# basic_schematic.net
KiCad netlist of a schematic drawn in EAGLE
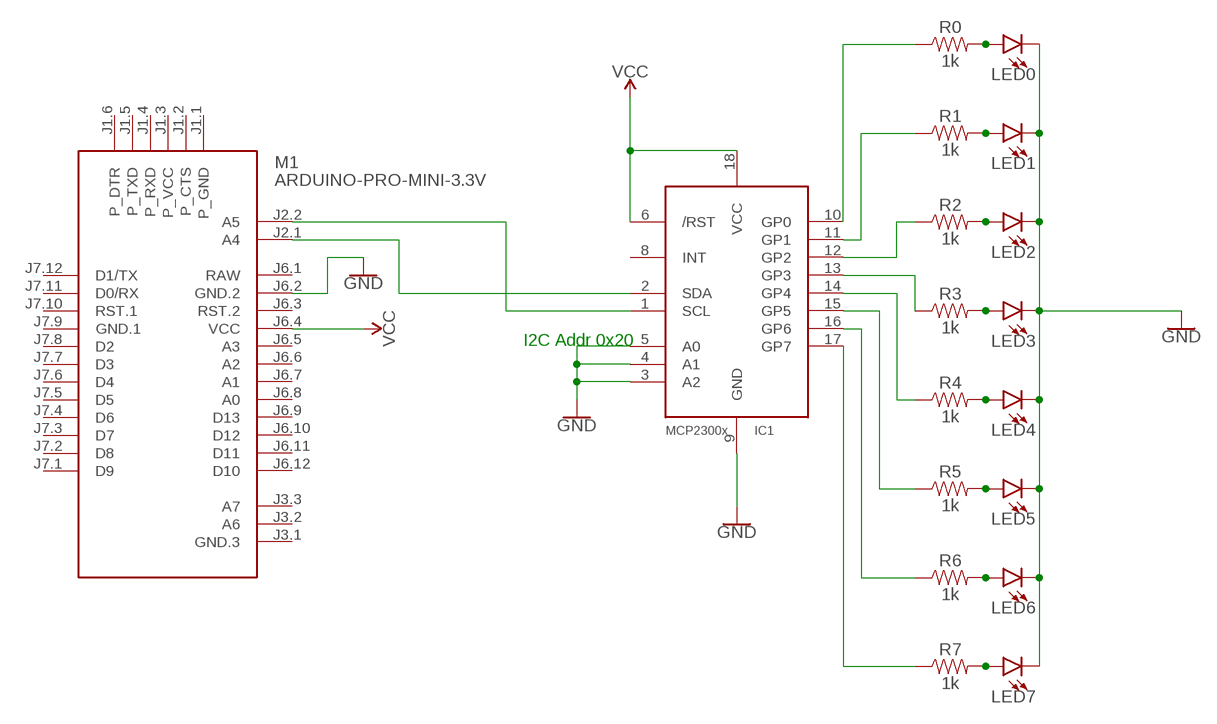
[diagram p0: schematic, sheet 1]

(export (version "E")
  (design (tool "Eeschema 10.0.6"))
  (components
    (comp (ref "IC1")
      (value "MCP23008/SO")
      (footprint "eagle-import:SO18W")
      (libsource (lib "eagle-import") (part "MCP23008/SO"))
    )
    (comp (ref "LED0")
      (value "LED3MM")
      (footprint "eagle-import:LED_3MM")
      (libsource (lib "eagle-import") (part "LED3MM"))
    )
    (comp (ref "LED1")
      (value "LED3MM")
      (footprint "eagle-import:LED_3MM")
      (libsource (lib "eagle-import") (part "LED3MM"))
    )
    (comp (ref "LED2")
      (value "LED3MM")
      (footprint "eagle-import:LED_3MM")
      (libsource (lib "eagle-import") (part "LED3MM"))
    )
    (comp (ref "LED3")
      (value "LED3MM")
      (footprint "eagle-import:LED_3MM")
      (libsource (lib "eagle-import") (part "LED3MM"))
    )
    (comp (ref "LED4")
      (value "LED3MM")
      (footprint "eagle-import:LED_3MM")
      (libsource (lib "eagle-import") (part "LED3MM"))
    )
    (comp (ref "LED5")
      (value "LED3MM")
      (footprint "eagle-import:LED_3MM")
      (libsource (lib "eagle-import") (part "LED3MM"))
    )
    (comp (ref "LED6")
      (value "LED3MM")
      (footprint "eagle-import:LED_3MM")
      (libsource (lib "eagle-import") (part "LED3MM"))
    )
    (comp (ref "LED7")
      (value "LED3MM")
      (footprint "eagle-import:LED_3MM")
      (libsource (lib "eagle-import") (part "LED3MM"))
    )
    (comp (ref "M1")
      (value "ARDUINO-PRO-MINI-3.3V")
      (footprint "eagle-import:ARDUINO-PRO-MINI")
      (libsource (lib "eagle-import") (part "ARDUINO-PRO-MINI-3.3V"))
    )
    (comp (ref "R0")
      (value "1k")
      (footprint "eagle-import:0603")
      (libsource (lib "eagle-import") (part "1KOHM-0603-1/10W-1%"))
    )
    (comp (ref "R1")
      (value "1k")
      (footprint "eagle-import:0603")
      (libsource (lib "eagle-import") (part "1KOHM-0603-1/10W-1%"))
    )
    (comp (ref "R2")
      (value "1k")
      (footprint "eagle-import:0603")
      (libsource (lib "eagle-import") (part "1KOHM-0603-1/10W-1%"))
    )
    (comp (ref "R3")
      (value "1k")
      (footprint "eagle-import:0603")
      (libsource (lib "eagle-import") (part "1KOHM-0603-1/10W-1%"))
    )
    (comp (ref "R4")
      (value "1k")
      (footprint "eagle-import:0603")
      (libsource (lib "eagle-import") (part "1KOHM-0603-1/10W-1%"))
    )
    (comp (ref "R5")
      (value "1k")
      (footprint "eagle-import:0603")
      (libsource (lib "eagle-import") (part "1KOHM-0603-1/10W-1%"))
    )
    (comp (ref "R6")
      (value "1k")
      (footprint "eagle-import:0603")
      (libsource (lib "eagle-import") (part "1KOHM-0603-1/10W-1%"))
    )
    (comp (ref "R7")
      (value "1k")
      (footprint "eagle-import:0603")
      (libsource (lib "eagle-import") (part "1KOHM-0603-1/10W-1%"))
    )
  )
  (nets
    (net (code "1") (name "/GND.1") (class "Default")
      (node (ref "M1") (pin "J7.9") (pinfunction "GND.1_J7.9") (pintype "power_in"))
    )
    (net (code "2") (name "/RAW") (class "Default")
      (node (ref "M1") (pin "J6.1") (pinfunction "RAW_J6.1") (pintype "power_in"))
    )
    (net (code "3") (name "GND") (class "Default")
      (node (ref "IC1") (pin "3") (pinfunction "A2_3") (pintype "input"))
      (node (ref "IC1") (pin "4") (pinfunction "A1_4") (pintype "input"))
      (node (ref "IC1") (pin "5") (pinfunction "A0_5") (pintype "input"))
      (node (ref "IC1") (pin "9") (pinfunction "GND_9") (pintype "power_in"))
      (node (ref "LED0") (pin "K") (pinfunction "C_K") (pintype "passive"))
      (node (ref "LED1") (pin "K") (pinfunction "C_K") (pintype "passive"))
      (node (ref "LED2") (pin "K") (pinfunction "C_K") (pintype "passive"))
      (node (ref "LED3") (pin "K") (pinfunction "C_K") (pintype "passive"))
      (node (ref "LED4") (pin "K") (pinfunction "C_K") (pintype "passive"))
      (node (ref "LED5") (pin "K") (pinfunction "C_K") (pintype "passive"))
      (node (ref "LED6") (pin "K") (pinfunction "C_K") (pintype "passive"))
      (node (ref "LED7") (pin "K") (pinfunction "C_K") (pintype "passive"))
      (node (ref "M1") (pin "J6.2") (pinfunction "GND.2_J6.2") (pintype "power_in"))
    )
    (net (code "4") (name "Net-(IC1-GP0)") (class "Default")
      (node (ref "IC1") (pin "10") (pinfunction "GP0_10") (pintype "bidirectional"))
      (node (ref "R0") (pin "1") (pinfunction "1_1") (pintype "passive"))
    )
    (net (code "5") (name "Net-(IC1-GP1)") (class "Default")
      (node (ref "IC1") (pin "11") (pinfunction "GP1_11") (pintype "bidirectional"))
      (node (ref "R1") (pin "1") (pinfunction "1_1") (pintype "passive"))
    )
    (net (code "6") (name "Net-(IC1-GP2)") (class "Default")
      (node (ref "IC1") (pin "12") (pinfunction "GP2_12") (pintype "bidirectional"))
      (node (ref "R2") (pin "1") (pinfunction "1_1") (pintype "passive"))
    )
    (net (code "7") (name "Net-(IC1-GP3)") (class "Default")
      (node (ref "IC1") (pin "13") (pinfunction "GP3_13") (pintype "bidirectional"))
      (node (ref "R3") (pin "1") (pinfunction "1_1") (pintype "passive"))
    )
    (net (code "8") (name "Net-(IC1-GP4)") (class "Default")
      (node (ref "IC1") (pin "14") (pinfunction "GP4_14") (pintype "bidirectional"))
      (node (ref "R4") (pin "1") (pinfunction "1_1") (pintype "passive"))
    )
    (net (code "9") (name "Net-(IC1-GP5)") (class "Default")
      (node (ref "IC1") (pin "15") (pinfunction "GP5_15") (pintype "bidirectional"))
      (node (ref "R5") (pin "1") (pinfunction "1_1") (pintype "passive"))
    )
    (net (code "10") (name "Net-(IC1-GP6)") (class "Default")
      (node (ref "IC1") (pin "16") (pinfunction "GP6_16") (pintype "bidirectional"))
      (node (ref "R6") (pin "1") (pinfunction "1_1") (pintype "passive"))
    )
    (net (code "11") (name "Net-(IC1-GP7)") (class "Default")
      (node (ref "IC1") (pin "17") (pinfunction "GP7_17") (pintype "bidirectional"))
      (node (ref "R7") (pin "1") (pinfunction "1_1") (pintype "passive"))
    )
    (net (code "12") (name "Net-(IC1-SCL)") (class "Default")
      (node (ref "IC1") (pin "1") (pinfunction "SCL_1") (pintype "bidirectional"))
      (node (ref "M1") (pin "J2.2") (pinfunction "A5_J2.2") (pintype "bidirectional"))
    )
    (net (code "13") (name "Net-(IC1-SDA)") (class "Default")
      (node (ref "IC1") (pin "2") (pinfunction "SDA_2") (pintype "bidirectional"))
      (node (ref "M1") (pin "J2.1") (pinfunction "A4_J2.1") (pintype "bidirectional"))
    )
    (net (code "14") (name "Net-(LED0-PadA)") (class "Default")
      (node (ref "LED0") (pin "A") (pinfunction "A_A") (pintype "passive"))
      (node (ref "R0") (pin "2") (pinfunction "2_2") (pintype "passive"))
    )
    (net (code "15") (name "Net-(LED1-PadA)") (class "Default")
      (node (ref "LED1") (pin "A") (pinfunction "A_A") (pintype "passive"))
      (node (ref "R1") (pin "2") (pinfunction "2_2") (pintype "passive"))
    )
    (net (code "16") (name "Net-(LED2-PadA)") (class "Default")
      (node (ref "LED2") (pin "A") (pinfunction "A_A") (pintype "passive"))
      (node (ref "R2") (pin "2") (pinfunction "2_2") (pintype "passive"))
    )
    (net (code "17") (name "Net-(LED3-PadA)") (class "Default")
      (node (ref "LED3") (pin "A") (pinfunction "A_A") (pintype "passive"))
      (node (ref "R3") (pin "2") (pinfunction "2_2") (pintype "passive"))
    )
    (net (code "18") (name "Net-(LED4-PadA)") (class "Default")
      (node (ref "LED4") (pin "A") (pinfunction "A_A") (pintype "passive"))
      (node (ref "R4") (pin "2") (pinfunction "2_2") (pintype "passive"))
    )
    (net (code "19") (name "Net-(LED5-PadA)") (class "Default")
      (node (ref "LED5") (pin "A") (pinfunction "A_A") (pintype "passive"))
      (node (ref "R5") (pin "2") (pinfunction "2_2") (pintype "passive"))
    )
    (net (code "20") (name "Net-(LED6-PadA)") (class "Default")
      (node (ref "LED6") (pin "A") (pinfunction "A_A") (pintype "passive"))
      (node (ref "R6") (pin "2") (pinfunction "2_2") (pintype "passive"))
    )
    (net (code "21") (name "Net-(LED7-PadA)") (class "Default")
      (node (ref "LED7") (pin "A") (pinfunction "A_A") (pintype "passive"))
      (node (ref "R7") (pin "2") (pinfunction "2_2") (pintype "passive"))
    )
    (net (code "22") (name "VCC") (class "Default")
      (node (ref "IC1") (pin "18") (pinfunction "VCC_18") (pintype "power_in"))
      (node (ref "IC1") (pin "6") (pinfunction "/RST_6") (pintype "input"))
      (node (ref "M1") (pin "J6.4") (pinfunction "VCC_J6.4") (pintype "power_in"))
    )
    (net (code "23") (name "unconnected-(IC1-INT-Pad8)") (class "Default")
      (node (ref "IC1") (pin "8") (pinfunction "INT_8") (pintype "output"))
    )
    (net (code "24") (name "unconnected-(M1-A0-PadJ6.8)") (class "Default")
      (node (ref "M1") (pin "J6.8") (pinfunction "A0_J6.8") (pintype "bidirectional"))
    )
    (net (code "25") (name "unconnected-(M1-A1-PadJ6.7)") (class "Default")
      (node (ref "M1") (pin "J6.7") (pinfunction "A1_J6.7") (pintype "bidirectional"))
    )
    (net (code "26") (name "unconnected-(M1-A2-PadJ6.6)") (class "Default")
      (node (ref "M1") (pin "J6.6") (pinfunction "A2_J6.6") (pintype "bidirectional"))
    )
    (net (code "27") (name "unconnected-(M1-A3-PadJ6.5)") (class "Default")
      (node (ref "M1") (pin "J6.5") (pinfunction "A3_J6.5") (pintype "bidirectional"))
    )
    (net (code "28") (name "unconnected-(M1-A6-PadJ3.2)") (class "Default")
      (node (ref "M1") (pin "J3.2") (pinfunction "A6_J3.2") (pintype "bidirectional"))
    )
    (net (code "29") (name "unconnected-(M1-A7-PadJ3.3)") (class "Default")
      (node (ref "M1") (pin "J3.3") (pinfunction "A7_J3.3") (pintype "bidirectional"))
    )
    (net (code "30") (name "unconnected-(M1-D0{slash}RX-PadJ7.11)") (class "Default")
      (node (ref "M1") (pin "J7.11") (pinfunction "D0/RX_J7.11") (pintype "bidirectional"))
    )
    (net (code "31") (name "unconnected-(M1-D1{slash}TX-PadJ7.12)") (class "Default")
      (node (ref "M1") (pin "J7.12") (pinfunction "D1/TX_J7.12") (pintype "bidirectional"))
    )
    (net (code "32") (name "unconnected-(M1-D2-PadJ7.8)") (class "Default")
      (node (ref "M1") (pin "J7.8") (pinfunction "D2_J7.8") (pintype "bidirectional"))
    )
    (net (code "33") (name "unconnected-(M1-D3-PadJ7.7)") (class "Default")
      (node (ref "M1") (pin "J7.7") (pinfunction "D3_J7.7") (pintype "bidirectional"))
    )
    (net (code "34") (name "unconnected-(M1-D4-PadJ7.6)") (class "Default")
      (node (ref "M1") (pin "J7.6") (pinfunction "D4_J7.6") (pintype "bidirectional"))
    )
    (net (code "35") (name "unconnected-(M1-D5-PadJ7.5)") (class "Default")
      (node (ref "M1") (pin "J7.5") (pinfunction "D5_J7.5") (pintype "bidirectional"))
    )
    (net (code "36") (name "unconnected-(M1-D6-PadJ7.4)") (class "Default")
      (node (ref "M1") (pin "J7.4") (pinfunction "D6_J7.4") (pintype "bidirectional"))
    )
    (net (code "37") (name "unconnected-(M1-D7-PadJ7.3)") (class "Default")
      (node (ref "M1") (pin "J7.3") (pinfunction "D7_J7.3") (pintype "bidirectional"))
    )
    (net (code "38") (name "unconnected-(M1-D8-PadJ7.2)") (class "Default")
      (node (ref "M1") (pin "J7.2") (pinfunction "D8_J7.2") (pintype "bidirectional"))
    )
    (net (code "39") (name "unconnected-(M1-D9-PadJ7.1)") (class "Default")
      (node (ref "M1") (pin "J7.1") (pinfunction "D9_J7.1") (pintype "bidirectional"))
    )
    (net (code "40") (name "unconnected-(M1-D10-PadJ6.12)") (class "Default")
      (node (ref "M1") (pin "J6.12") (pinfunction "D10_J6.12") (pintype "bidirectional"))
    )
    (net (code "41") (name "unconnected-(M1-D11-PadJ6.11)") (class "Default")
      (node (ref "M1") (pin "J6.11") (pinfunction "D11_J6.11") (pintype "bidirectional"))
    )
    (net (code "42") (name "unconnected-(M1-D12-PadJ6.10)") (class "Default")
      (node (ref "M1") (pin "J6.10") (pinfunction "D12_J6.10") (pintype "bidirectional"))
    )
    (net (code "43") (name "unconnected-(M1-D13-PadJ6.9)") (class "Default")
      (node (ref "M1") (pin "J6.9") (pinfunction "D13_J6.9") (pintype "bidirectional"))
    )
    (net (code "44") (name "unconnected-(M1-GND.3-PadJ3.1)") (class "Default")
      (node (ref "M1") (pin "J3.1") (pinfunction "GND.3_J3.1") (pintype "bidirectional"))
    )
    (net (code "45") (name "unconnected-(M1-P_CTS-PadJ1.2)") (class "Default")
      (node (ref "M1") (pin "J1.2") (pinfunction "P_CTS_J1.2") (pintype "bidirectional"))
    )
    (net (code "46") (name "unconnected-(M1-P_DTR-PadJ1.6)") (class "Default")
      (node (ref "M1") (pin "J1.6") (pinfunction "P_DTR_J1.6") (pintype "bidirectional"))
    )
    (net (code "47") (name "unconnected-(M1-P_GND-PadJ1.1)") (class "Default")
      (node (ref "M1") (pin "J1.1") (pinfunction "P_GND_J1.1") (pintype "bidirectional"))
    )
    (net (code "48") (name "unconnected-(M1-P_RXD-PadJ1.4)") (class "Default")
      (node (ref "M1") (pin "J1.4") (pinfunction "P_RXD_J1.4") (pintype "bidirectional"))
    )
    (net (code "49") (name "unconnected-(M1-P_TXD-PadJ1.5)") (class "Default")
      (node (ref "M1") (pin "J1.5") (pinfunction "P_TXD_J1.5") (pintype "bidirectional"))
    )
    (net (code "50") (name "unconnected-(M1-P_VCC-PadJ1.3)") (class "Default")
      (node (ref "M1") (pin "J1.3") (pinfunction "P_VCC_J1.3") (pintype "bidirectional"))
    )
    (net (code "51") (name "unconnected-(M1-RST.1-PadJ7.10)") (class "Default")
      (node (ref "M1") (pin "J7.10") (pinfunction "RST.1_J7.10") (pintype "bidirectional"))
    )
    (net (code "52") (name "unconnected-(M1-RST.2-PadJ6.3)") (class "Default")
      (node (ref "M1") (pin "J6.3") (pinfunction "RST.2_J6.3") (pintype "bidirectional"))
    )
  )
)
